# VF_FabricaDeUnicorniosMuertos_PCB.net
KiCad netlist of a schematic drawn in EAGLE
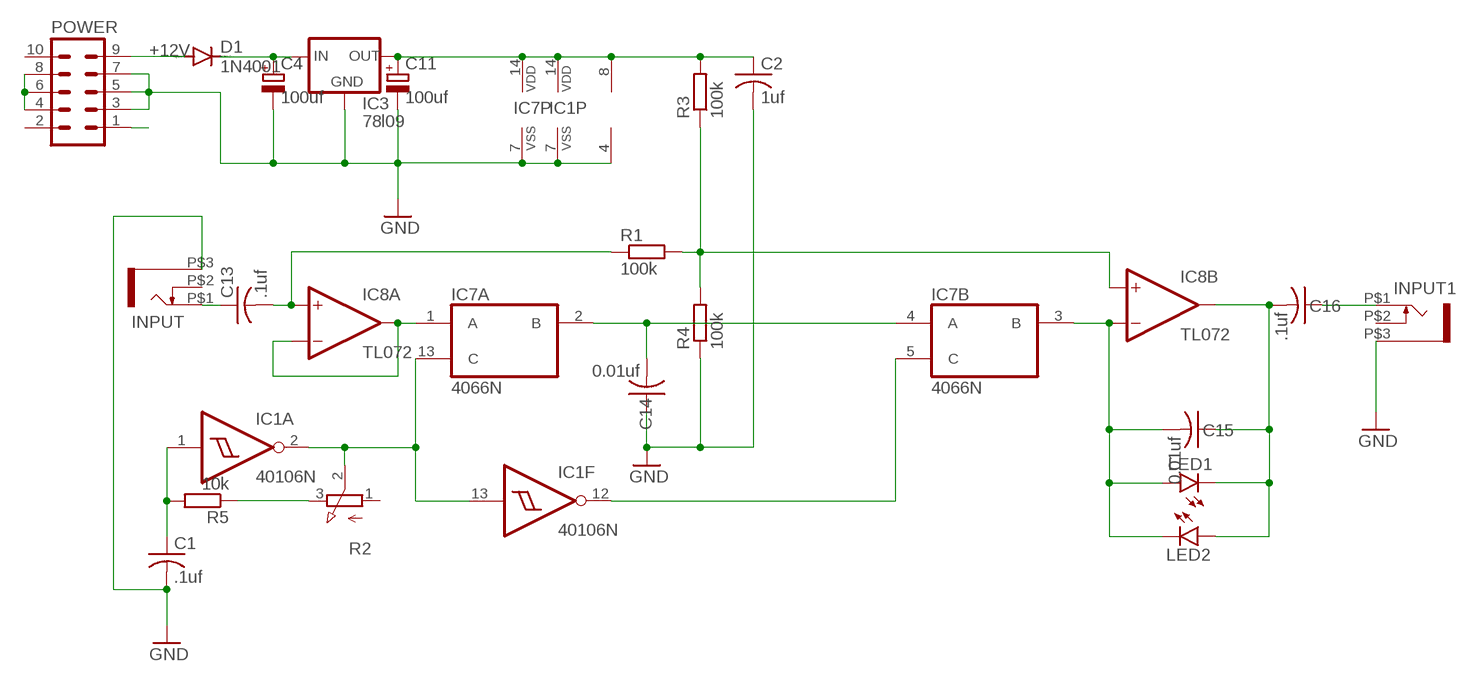
[diagram p0: schematic, sheet 1]

(export (version "E")
  (design (tool "Eeschema 10.0.6"))
  (components
    (comp (ref "C1")
      (value ".1uf")
      (footprint "eagle-import:C050-025X075")
      (libsource (lib "eagle-import") (part "C-US050-025X075"))
    )
    (comp (ref "C2")
      (value "1uf")
      (footprint "eagle-import:C050-025X075")
      (libsource (lib "eagle-import") (part "C-US050-025X075"))
    )
    (comp (ref "C4")
      (value "100uf")
      (footprint "eagle-import:E2,5-7")
      (libsource (lib "eagle-import") (part "CPOL-EUE2.5-7"))
    )
    (comp (ref "C11")
      (value "100uf")
      (footprint "eagle-import:E2,5-7")
      (libsource (lib "eagle-import") (part "CPOL-EUE2.5-7"))
    )
    (comp (ref "C13")
      (value ".1uf")
      (footprint "eagle-import:C050-025X075")
      (libsource (lib "eagle-import") (part "C-US050-025X075"))
    )
    (comp (ref "C14")
      (value "0.01uf")
      (footprint "eagle-import:C050-025X075")
      (libsource (lib "eagle-import") (part "C-US050-025X075"))
    )
    (comp (ref "C15")
      (value "0.01uf")
      (footprint "eagle-import:C050-025X075")
      (libsource (lib "eagle-import") (part "C-US050-025X075"))
    )
    (comp (ref "C16")
      (value ".1uf")
      (footprint "eagle-import:C050-025X075")
      (libsource (lib "eagle-import") (part "C-US050-025X075"))
    )
    (comp (ref "D1")
      (value "1N4001")
      (footprint "eagle-import:DO41-10")
      (libsource (lib "eagle-import") (part "1N4004"))
    )
    (comp (ref "IC1")
      (value "40106N")
      (footprint "eagle-import:DIL14")
      (libsource (lib "eagle-import") (part "40106N"))
    )
    (comp (ref "IC3")
      (value "78l09")
      (footprint "eagle-import:78LXX")
      (libsource (lib "eagle-import") (part "78LXX"))
    )
    (comp (ref "IC7")
      (value "4066N")
      (footprint "eagle-import:DIL14")
      (libsource (lib "eagle-import") (part "4066N"))
    )
    (comp (ref "IC8")
      (value "TL072")
      (footprint "eagle-import:DIL08")
      (libsource (lib "eagle-import") (part "MCP6002DIL_LONG"))
    )
    (comp (ref "INPUT")
      (value "WQP-PJ301M-12_JACK")
      (footprint "eagle-import:WQP-PJ301M-12_JACK")
      (libsource (lib "eagle-import") (part "WQP-PJ301M-12_JACK"))
    )
    (comp (ref "INPUT1")
      (value "WQP-PJ301M-12_JACK")
      (footprint "eagle-import:WQP-PJ301M-12_JACK")
      (libsource (lib "eagle-import") (part "WQP-PJ301M-12_JACK"))
    )
    (comp (ref "LED1")
      (value "LED3MM")
      (footprint "eagle-import:LED3MM")
      (libsource (lib "eagle-import") (part "LED3MM"))
    )
    (comp (ref "LED2")
      (value "LED3MM")
      (footprint "eagle-import:LED3MM")
      (libsource (lib "eagle-import") (part "LED3MM"))
    )
    (comp (ref "POWER")
      (value "10_PIN_HEADER")
      (footprint "eagle-import:MA05-2")
      (libsource (lib "eagle-import") (part "10_PIN_HEADER"))
    )
    (comp (ref "R1")
      (value "100k")
      (footprint "eagle-import:7MM_RESISTOR")
      (libsource (lib "eagle-import") (part "RESISTOR7MM"))
    )
    (comp (ref "R2")
      (value "EVUF2L")
      (footprint "eagle-import:EVUFXL")
      (libsource (lib "eagle-import") (part "EVULF2"))
    )
    (comp (ref "R3")
      (value "100k")
      (footprint "eagle-import:7MM_RESISTOR")
      (libsource (lib "eagle-import") (part "RESISTOR7MM"))
    )
    (comp (ref "R4")
      (value "100k")
      (footprint "eagle-import:7MM_RESISTOR")
      (libsource (lib "eagle-import") (part "RESISTOR7MM"))
    )
    (comp (ref "R5")
      (value "10k")
      (footprint "eagle-import:7MM_RESISTOR")
      (libsource (lib "eagle-import") (part "RESISTOR7MM"))
    )
  )
  (nets
    (net (code "1") (name "/+12V") (class "Default")
      (node (ref "C4") (pin "+") (pinfunction "+_+") (pintype "passive"))
      (node (ref "D1") (pin "C") (pinfunction "C_C") (pintype "passive"))
      (node (ref "IC3") (pin "IN") (pinfunction "IN_IN") (pintype "input"))
    )
    (net (code "2") (name "GND") (class "Default")
      (node (ref "C1") (pin "2") (pinfunction "2_2") (pintype "passive"))
      (node (ref "C11") (pin "-") (pinfunction "-_-") (pintype "passive"))
      (node (ref "C14") (pin "1") (pinfunction "1_1") (pintype "passive"))
      (node (ref "C2") (pin "2") (pinfunction "2_2") (pintype "passive"))
      (node (ref "C4") (pin "-") (pinfunction "-_-") (pintype "passive"))
      (node (ref "IC1") (pin "7") (pinfunction "VSS_7") (pintype "power_in"))
      (node (ref "IC3") (pin "GND") (pinfunction "GND_GND") (pintype "input"))
      (node (ref "IC7") (pin "7") (pinfunction "VSS_7") (pintype "power_in"))
      (node (ref "IC8") (pin "4") (pinfunction "V-_4") (pintype "power_in"))
      (node (ref "INPUT") (pin "P$3") (pinfunction "1_P$3") (pintype "passive"))
      (node (ref "INPUT1") (pin "P$3") (pinfunction "1_P$3") (pintype "passive"))
      (node (ref "POWER") (pin "3") (pinfunction "3_3") (pintype "passive"))
      (node (ref "POWER") (pin "5") (pinfunction "5_5") (pintype "passive"))
      (node (ref "POWER") (pin "7") (pinfunction "7_7") (pintype "passive"))
      (node (ref "R4") (pin "1") (pinfunction "1_1") (pintype "passive"))
    )
    (net (code "3") (name "Net-(D1-PadA)") (class "Default")
      (node (ref "D1") (pin "A") (pinfunction "A_A") (pintype "passive"))
      (node (ref "POWER") (pin "9") (pinfunction "9_9") (pintype "passive"))
    )
    (net (code "4") (name "Net-(IC1A-I)") (class "Default")
      (node (ref "C1") (pin "1") (pinfunction "1_1") (pintype "passive"))
      (node (ref "IC1") (pin "1") (pinfunction "I_1") (pintype "input"))
      (node (ref "R5") (pin "2") (pinfunction "2_2") (pintype "passive"))
    )
    (net (code "5") (name "Net-(IC1A-O)") (class "Default")
      (node (ref "IC1") (pin "13") (pinfunction "I_13") (pintype "input"))
      (node (ref "IC1") (pin "2") (pinfunction "O_2") (pintype "output"))
      (node (ref "IC7") (pin "13") (pinfunction "C_13") (pintype "input"))
      (node (ref "R2") (pin "2") (pinfunction "S_2") (pintype "passive"))
    )
    (net (code "6") (name "Net-(IC1F-O)") (class "Default")
      (node (ref "IC1") (pin "12") (pinfunction "O_12") (pintype "output"))
      (node (ref "IC7") (pin "5") (pinfunction "C_5") (pintype "input"))
    )
    (net (code "7") (name "Net-(IC1G-VDD)") (class "Default")
      (node (ref "C11") (pin "+") (pinfunction "+_+") (pintype "passive"))
      (node (ref "C2") (pin "1") (pinfunction "1_1") (pintype "passive"))
      (node (ref "IC1") (pin "14") (pinfunction "VDD_14") (pintype "power_in"))
      (node (ref "IC3") (pin "OUT") (pinfunction "OUT_OUT") (pintype "passive"))
      (node (ref "IC7") (pin "14") (pinfunction "VDD_14") (pintype "power_in"))
      (node (ref "IC8") (pin "8") (pinfunction "V+_8") (pintype "power_in"))
      (node (ref "R3") (pin "2") (pinfunction "2_2") (pintype "passive"))
    )
    (net (code "8") (name "Net-(IC7A-A)") (class "Default")
      (node (ref "IC7") (pin "1") (pinfunction "A_1") (pintype "tri_state"))
      (node (ref "IC8") (pin "1") (pinfunction "OUT_1") (pintype "output"))
      (node (ref "IC8") (pin "2") (pinfunction "-IN_2") (pintype "input"))
    )
    (net (code "9") (name "Net-(IC7A-B)") (class "Default")
      (node (ref "C14") (pin "2") (pinfunction "2_2") (pintype "passive"))
      (node (ref "IC7") (pin "2") (pinfunction "B_2") (pintype "tri_state"))
      (node (ref "IC7") (pin "4") (pinfunction "A_4") (pintype "tri_state"))
    )
    (net (code "10") (name "Net-(IC7B-B)") (class "Default")
      (node (ref "C15") (pin "2") (pinfunction "2_2") (pintype "passive"))
      (node (ref "IC7") (pin "3") (pinfunction "B_3") (pintype "tri_state"))
      (node (ref "IC8") (pin "6") (pinfunction "-IN_6") (pintype "input"))
      (node (ref "LED1") (pin "A") (pinfunction "A_A") (pintype "passive"))
      (node (ref "LED2") (pin "K") (pinfunction "C_K") (pintype "passive"))
    )
    (net (code "11") (name "Net-(IC8A-+IN)") (class "Default")
      (node (ref "C13") (pin "2") (pinfunction "2_2") (pintype "passive"))
      (node (ref "IC8") (pin "3") (pinfunction "+IN_3") (pintype "input"))
      (node (ref "R1") (pin "1") (pinfunction "1_1") (pintype "passive"))
    )
    (net (code "12") (name "Net-(IC8B-+IN)") (class "Default")
      (node (ref "IC8") (pin "5") (pinfunction "+IN_5") (pintype "input"))
      (node (ref "R1") (pin "2") (pinfunction "2_2") (pintype "passive"))
      (node (ref "R3") (pin "1") (pinfunction "1_1") (pintype "passive"))
      (node (ref "R4") (pin "2") (pinfunction "2_2") (pintype "passive"))
    )
    (net (code "13") (name "Net-(IC8B-OUT)") (class "Default")
      (node (ref "C15") (pin "1") (pinfunction "1_1") (pintype "passive"))
      (node (ref "C16") (pin "2") (pinfunction "2_2") (pintype "passive"))
      (node (ref "IC8") (pin "7") (pinfunction "OUT_7") (pintype "output"))
      (node (ref "LED1") (pin "K") (pinfunction "C_K") (pintype "passive"))
      (node (ref "LED2") (pin "A") (pinfunction "A_A") (pintype "passive"))
    )
    (net (code "14") (name "Net-(INPUT-2)") (class "Default")
      (node (ref "C13") (pin "1") (pinfunction "1_1") (pintype "passive"))
      (node (ref "INPUT") (pin "P$1") (pinfunction "2_P$1") (pintype "passive"))
    )
    (net (code "15") (name "Net-(INPUT1-2)") (class "Default")
      (node (ref "C16") (pin "1") (pinfunction "1_1") (pintype "passive"))
      (node (ref "INPUT1") (pin "P$1") (pinfunction "2_P$1") (pintype "passive"))
    )
    (net (code "16") (name "Net-(POWER-Pad4)") (class "Default")
      (node (ref "POWER") (pin "4") (pinfunction "4_4") (pintype "passive"))
      (node (ref "POWER") (pin "6") (pinfunction "6_6") (pintype "passive"))
      (node (ref "POWER") (pin "8") (pinfunction "8_8") (pintype "passive"))
    )
    (net (code "17") (name "Net-(R2-E)") (class "Default")
      (node (ref "R2") (pin "3") (pinfunction "E_3") (pintype "passive"))
      (node (ref "R5") (pin "1") (pinfunction "1_1") (pintype "passive"))
    )
    (net (code "18") (name "unconnected-(INPUT-3-PadP$2)") (class "Default")
      (node (ref "INPUT") (pin "P$2") (pinfunction "3_P$2") (pintype "passive"))
    )
    (net (code "19") (name "unconnected-(INPUT1-3-PadP$2)") (class "Default")
      (node (ref "INPUT1") (pin "P$2") (pinfunction "3_P$2") (pintype "passive"))
    )
    (net (code "20") (name "unconnected-(POWER-Pad1)") (class "Default")
      (node (ref "POWER") (pin "1") (pinfunction "1_1") (pintype "passive"))
    )
    (net (code "21") (name "unconnected-(POWER-Pad2)") (class "Default")
      (node (ref "POWER") (pin "2") (pinfunction "2_2") (pintype "passive"))
    )
    (net (code "22") (name "unconnected-(POWER-Pad10)") (class "Default")
      (node (ref "POWER") (pin "10") (pinfunction "10_10") (pintype "passive"))
    )
    (net (code "23") (name "unconnected-(R2-A-Pad1)") (class "Default")
      (node (ref "R2") (pin "1") (pinfunction "A_1") (pintype "passive"))
    )
  )
)
